# RF_and_GPS.net
KiCad netlist of a schematic drawn in Altium Designer
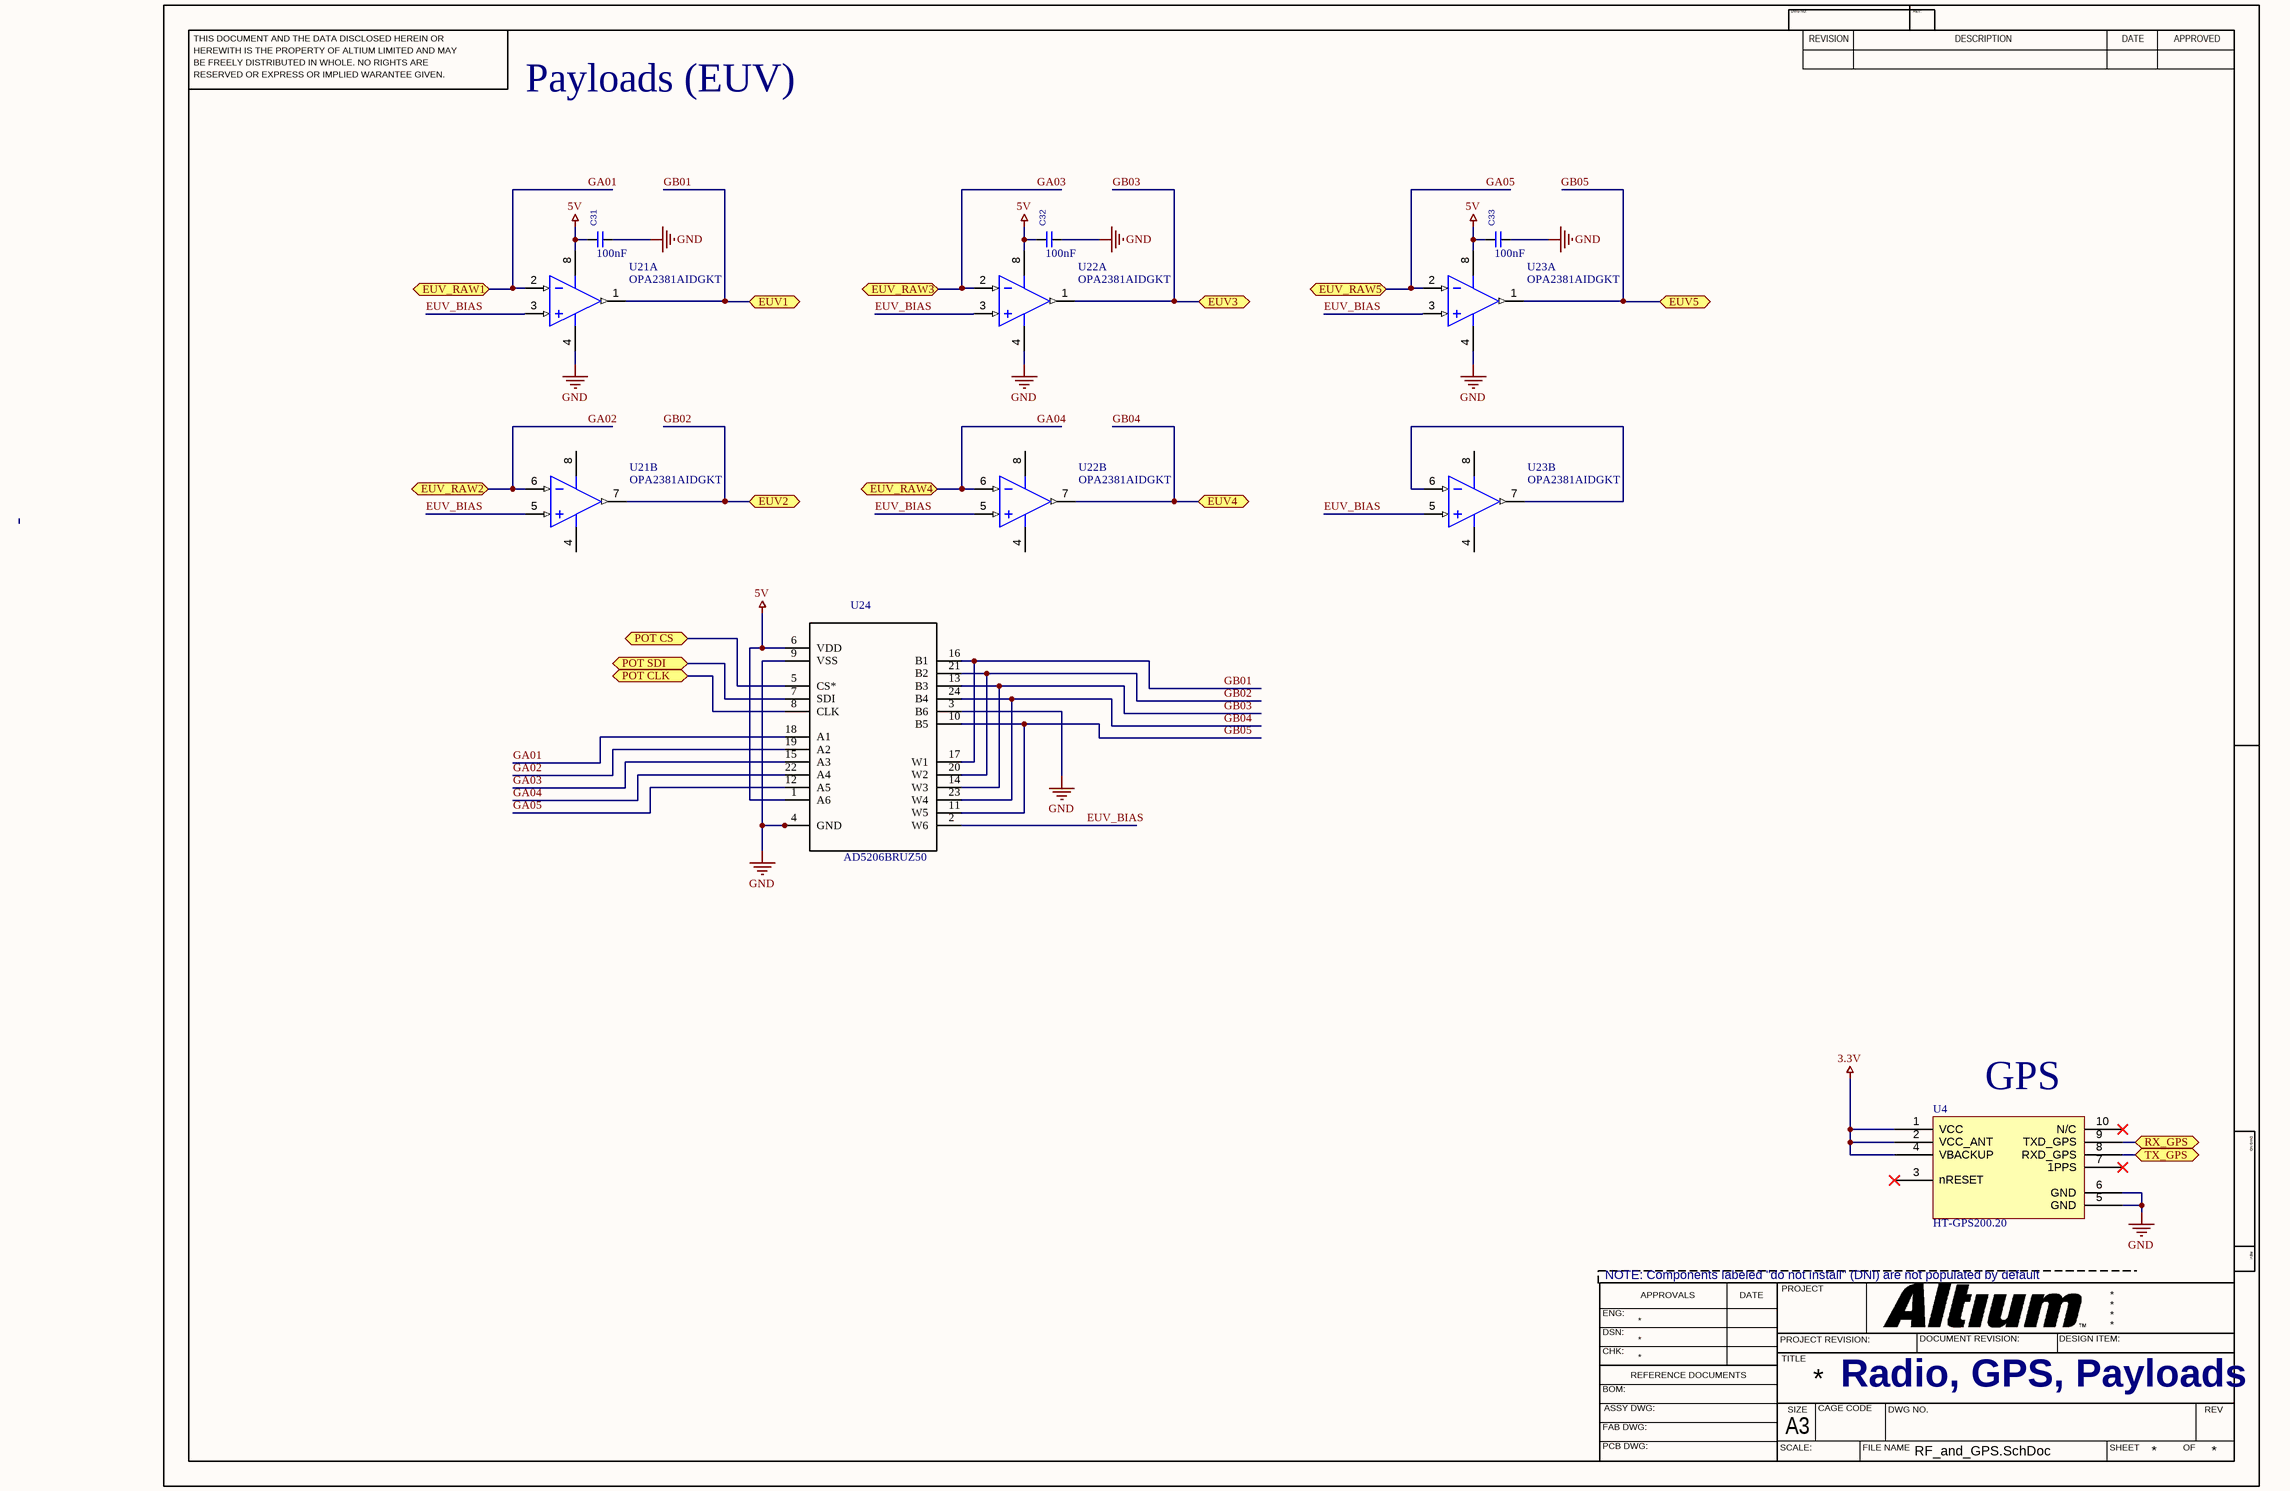
[diagram p0: RF_and_GPS.SchDoc]

(export (version "E")
  (design (tool "Eeschema 10.0.6"))
  (components
    (comp (ref "C31")
      (value "100nF")
      (footprint "Resistor_0805")
      (fields (field (name "MPN") "CL21B104KBCNNNC"))
      (libsource (lib "mainboard_1") (part "CL21B104KBCNNNC"))
    )
    (comp (ref "C32")
      (value "100nF")
      (footprint "Resistor_0805")
      (fields (field (name "MPN") "CL21B104KBCNNNC"))
      (libsource (lib "mainboard_1") (part "CL21B104KBCNNNC"))
    )
    (comp (ref "C33")
      (value "100nF")
      (footprint "Resistor_0805")
      (fields (field (name "MPN") "CL21B104KBCNNNC"))
      (libsource (lib "mainboard_1") (part "CL21B104KBCNNNC"))
    )
    (comp (ref "U4")
      (value "HT-GPS200.20")
      (footprint "HT-GPS200.20")
      (description "HT-GPS200.20 GNSS module")
      (libsource (lib "mainboard_1") (part "HT-GPS200.20"))
    )
    (comp (ref "U21")
      (value "OPA2381AIDGKT")
      (footprint "DGK0008A_N")
      (fields (field (name "MANUFACTURER") "Texas Instruments"))
      (libsource (lib "Altium Content Vault") (part "TI-OPA-8_2"))
    )
    (comp (ref "U22")
      (value "OPA2381AIDGKT")
      (footprint "DGK0008A_N")
      (fields (field (name "MANUFACTURER") "Texas Instruments"))
      (libsource (lib "Altium Content Vault") (part "TI-OPA-8_2"))
    )
    (comp (ref "U23")
      (value "OPA2381AIDGKT")
      (footprint "DGK0008A_N")
      (fields (field (name "MANUFACTURER") "Texas Instruments"))
      (libsource (lib "Altium Content Vault") (part "TI-OPA-8_2"))
    )
    (comp (ref "U24")
      (value "AD5206BRUZ50")
      (footprint "*SOP65P640X120-24N")
      (libsource (lib "AD5206BRUZ50") (part "AD5206BRUZ50"))
    )
  )
  (nets
    (net (code "1") (name "/EUV5") (class "Default")
      (node (ref "U23") (pin "1") (pinfunction "OUT_A_1") (pintype "output"))
    )
    (net (code "2") (name "/EUV_BIAS") (class "Default")
      (node (ref "U21") (pin "3") (pinfunction "IN_A+_3") (pintype "input"))
      (node (ref "U21") (pin "5") (pinfunction "IN_B+_5") (pintype "input"))
      (node (ref "U22") (pin "3") (pinfunction "IN_A+_3") (pintype "input"))
      (node (ref "U22") (pin "5") (pinfunction "IN_B+_5") (pintype "input"))
      (node (ref "U23") (pin "3") (pinfunction "IN_A+_3") (pintype "input"))
      (node (ref "U23") (pin "5") (pinfunction "IN_B+_5") (pintype "input"))
      (node (ref "U24") (pin "2") (pinfunction "W6_2") (pintype "passive"))
    )
    (net (code "3") (name "/GA01") (class "Default")
      (node (ref "U21") (pin "2") (pinfunction "IN_A-_2") (pintype "input"))
      (node (ref "U24") (pin "18") (pinfunction "A1_18") (pintype "passive"))
    )
    (net (code "4") (name "/GA02") (class "Default")
      (node (ref "U21") (pin "6") (pinfunction "IN_B-_6") (pintype "input"))
      (node (ref "U24") (pin "19") (pinfunction "A2_19") (pintype "passive"))
    )
    (net (code "5") (name "/GA03") (class "Default")
      (node (ref "U22") (pin "2") (pinfunction "IN_A-_2") (pintype "input"))
      (node (ref "U24") (pin "15") (pinfunction "A3_15") (pintype "passive"))
    )
    (net (code "6") (name "/GA04") (class "Default")
      (node (ref "U22") (pin "6") (pinfunction "IN_B-_6") (pintype "input"))
      (node (ref "U24") (pin "22") (pinfunction "A4_22") (pintype "passive"))
    )
    (net (code "7") (name "/GA05") (class "Default")
      (node (ref "U23") (pin "2") (pinfunction "IN_A-_2") (pintype "input"))
      (node (ref "U24") (pin "12") (pinfunction "A5_12") (pintype "passive"))
    )
    (net (code "8") (name "/GB01") (class "Default")
      (node (ref "U21") (pin "1") (pinfunction "OUT_A_1") (pintype "output"))
      (node (ref "U24") (pin "16") (pinfunction "B1_16") (pintype "passive"))
      (node (ref "U24") (pin "17") (pinfunction "W1_17") (pintype "passive"))
    )
    (net (code "9") (name "/GB02") (class "Default")
      (node (ref "U21") (pin "7") (pinfunction "OUT_B_7") (pintype "output"))
      (node (ref "U24") (pin "20") (pinfunction "W2_20") (pintype "passive"))
      (node (ref "U24") (pin "21") (pinfunction "B2_21") (pintype "passive"))
    )
    (net (code "10") (name "/GB03") (class "Default")
      (node (ref "U22") (pin "1") (pinfunction "OUT_A_1") (pintype "output"))
      (node (ref "U24") (pin "13") (pinfunction "B3_13") (pintype "passive"))
      (node (ref "U24") (pin "14") (pinfunction "W3_14") (pintype "passive"))
    )
    (net (code "11") (name "/GB04") (class "Default")
      (node (ref "U22") (pin "7") (pinfunction "OUT_B_7") (pintype "output"))
      (node (ref "U24") (pin "23") (pinfunction "W4_23") (pintype "passive"))
      (node (ref "U24") (pin "24") (pinfunction "B4_24") (pintype "passive"))
    )
    (net (code "12") (name "/GB05") (class "Default")
      (node (ref "U24") (pin "10") (pinfunction "B5_10") (pintype "passive"))
      (node (ref "U24") (pin "11") (pinfunction "W5_11") (pintype "passive"))
    )
    (net (code "13") (name "/POT CLK") (class "Default")
      (node (ref "U24") (pin "8") (pinfunction "CLK_8") (pintype "passive"))
    )
    (net (code "14") (name "/POT CS") (class "Default")
      (node (ref "U24") (pin "5") (pinfunction "CS*_5") (pintype "passive"))
    )
    (net (code "15") (name "/POT SDI") (class "Default")
      (node (ref "U24") (pin "7") (pinfunction "SDI_7") (pintype "passive"))
    )
    (net (code "16") (name "/RX_GPS") (class "Default")
      (node (ref "U4") (pin "9") (pinfunction "TXD_GPS_9") (pintype "passive"))
    )
    (net (code "17") (name "/TX_GPS") (class "Default")
      (node (ref "U4") (pin "8") (pinfunction "RXD_GPS_8") (pintype "passive"))
    )
    (net (code "18") (name "3.3V") (class "Default")
      (node (ref "U4") (pin "1") (pinfunction "VCC_1") (pintype "passive"))
      (node (ref "U4") (pin "2") (pinfunction "VCC_ANT_2") (pintype "passive"))
      (node (ref "U4") (pin "4") (pinfunction "VBACKUP_4") (pintype "passive"))
    )
    (net (code "19") (name "5V") (class "Default")
      (node (ref "C31") (pin "1") (pinfunction "1_1") (pintype "passive"))
      (node (ref "C32") (pin "1") (pinfunction "1_1") (pintype "passive"))
      (node (ref "C33") (pin "1") (pinfunction "1_1") (pintype "passive"))
      (node (ref "U21") (pin "8") (pinfunction "V+_8") (pintype "power_in"))
      (node (ref "U22") (pin "8") (pinfunction "V+_8") (pintype "power_in"))
      (node (ref "U23") (pin "8") (pinfunction "V+_8") (pintype "power_in"))
      (node (ref "U24") (pin "1") (pinfunction "A6_1") (pintype "passive"))
      (node (ref "U24") (pin "6") (pinfunction "VDD_6") (pintype "power_in"))
    )
    (net (code "20") (name "GND") (class "Default")
      (node (ref "C31") (pin "2") (pinfunction "2_2") (pintype "passive"))
      (node (ref "C32") (pin "2") (pinfunction "2_2") (pintype "passive"))
      (node (ref "C33") (pin "2") (pinfunction "2_2") (pintype "passive"))
      (node (ref "U21") (pin "4") (pinfunction "V-_4") (pintype "power_in"))
      (node (ref "U22") (pin "4") (pinfunction "V-_4") (pintype "power_in"))
      (node (ref "U23") (pin "4") (pinfunction "V-_4") (pintype "power_in"))
      (node (ref "U24") (pin "3") (pinfunction "B6_3") (pintype "passive"))
      (node (ref "U24") (pin "4") (pinfunction "GND_4") (pintype "power_in"))
      (node (ref "U24") (pin "9") (pinfunction "VSS_9") (pintype "power_in"))
      (node (ref "U4") (pin "5") (pinfunction "GND_5") (pintype "passive"))
      (node (ref "U4") (pin "6") (pinfunction "GND_6") (pintype "passive"))
    )
    (net (code "21") (name "Net-(U23B-IN_B-)") (class "Default")
      (node (ref "U23") (pin "6") (pinfunction "IN_B-_6") (pintype "input"))
      (node (ref "U23") (pin "7") (pinfunction "OUT_B_7") (pintype "output"))
    )
    (net (code "22") (name "unconnected-(U4-1PPS-Pad7)") (class "Default")
      (node (ref "U4") (pin "7") (pinfunction "1PPS_7") (pintype "passive+no_connect"))
    )
    (net (code "23") (name "unconnected-(U4-N{slash}C-Pad10)") (class "Default")
      (node (ref "U4") (pin "10") (pinfunction "N/C_10") (pintype "passive+no_connect"))
    )
    (net (code "24") (name "unconnected-(U4-nRESET-Pad3)") (class "Default")
      (node (ref "U4") (pin "3") (pinfunction "nRESET_3") (pintype "passive+no_connect"))
    )
    (net (code "25") (name "unconnected-(U21B-V+-Pad8)") (class "Default")
      (node (ref "U21") (pin "8") (pinfunction "V+_8") (pintype "power_in"))
    )
    (net (code "26") (name "unconnected-(U21B-V--Pad4)") (class "Default")
      (node (ref "U21") (pin "4") (pinfunction "V-_4") (pintype "power_in"))
    )
    (net (code "27") (name "unconnected-(U22B-V+-Pad8)") (class "Default")
      (node (ref "U22") (pin "8") (pinfunction "V+_8") (pintype "power_in"))
    )
    (net (code "28") (name "unconnected-(U22B-V--Pad4)") (class "Default")
      (node (ref "U22") (pin "4") (pinfunction "V-_4") (pintype "power_in"))
    )
    (net (code "29") (name "unconnected-(U23B-V+-Pad8)") (class "Default")
      (node (ref "U23") (pin "8") (pinfunction "V+_8") (pintype "power_in"))
    )
    (net (code "30") (name "unconnected-(U23B-V--Pad4)") (class "Default")
      (node (ref "U23") (pin "4") (pinfunction "V-_4") (pintype "power_in"))
    )
  )
)
